# Main.net
KiCad netlist of a schematic drawn in Altium Designer
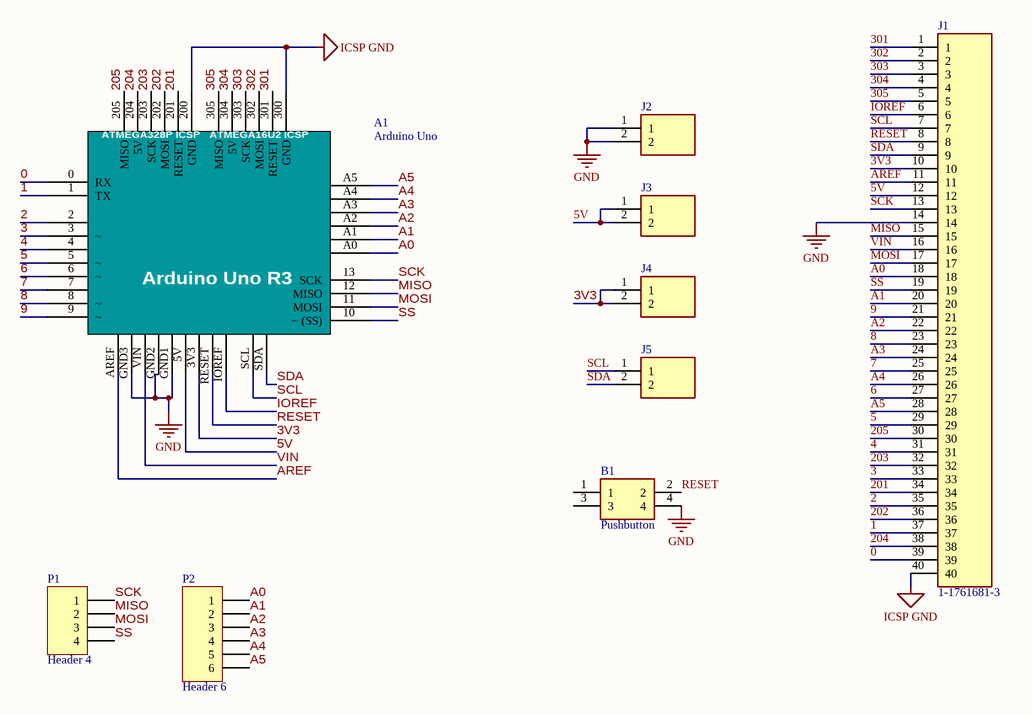
[diagram p0: Main.SchDoc]

(export (version "E")
  (design (tool "Eeschema 10.0.6"))
  (components
    (comp (ref "A1")
      (value "Arduino Uno")
      (footprint "Arduino Uno")
      (libsource (lib "Detailed Arduino") (part "Arduino Uno"))
    )
    (comp (ref "B1")
      (value "Pushbutton")
      (footprint "SamacSys:FSM4JH")
      (description "Switch")
      (fields
        (field (name "MANUFACTURER_PART_NUMBER") "FSM2JAH")
        (field (name "MOUSER PART NUMBER") "506-FSM2JAH")
      )
      (libsource (lib "SamacSys") (part "Pushbutton"))
    )
    (comp (ref "J1")
      (value "1-1761681-3")
      (footprint "TE_1-1761681-3")
      (description "IDC LOW PRO HDR 50P VERT HT BLACK")
      (libsource (lib "Molex 40pin Connector") (part "1-1761681-3"))
    )
    (comp (ref "J2")
      (value "TB002-500-02BE")
      (footprint "SamacSys:TB00250002BE")
      (description "Connector")
      (fields (field (name "MOUSER PART NUMBER") "490-TB002-500-02BE"))
      (libsource (lib "SamacSys") (part "TB002-500-02BE"))
    )
    (comp (ref "J3")
      (value "TB002-500-02BE")
      (footprint "SamacSys:TB00250002BE")
      (description "Connector")
      (fields (field (name "MOUSER PART NUMBER") "490-TB002-500-02BE"))
      (libsource (lib "SamacSys") (part "TB002-500-02BE"))
    )
    (comp (ref "J4")
      (value "TB002-500-02BE")
      (footprint "SamacSys:TB00250002BE")
      (description "Connector")
      (fields (field (name "MOUSER PART NUMBER") "490-TB002-500-02BE"))
      (libsource (lib "SamacSys") (part "TB002-500-02BE"))
    )
    (comp (ref "J5")
      (value "TB002-500-02BE")
      (footprint "SamacSys:TB00250002BE")
      (description "Connector")
      (fields (field (name "MOUSER PART NUMBER") "490-TB002-500-02BE"))
      (libsource (lib "SamacSys") (part "TB002-500-02BE"))
    )
    (comp (ref "P1")
      (value "Header 4")
      (footprint "HDR1X4")
      (description "Header, 4-Pin")
      (fields (field (name "PUBLISHER") "Altium Limited"))
      (libsource (lib "Miscellaneous Connectors") (part "Header 4"))
    )
    (comp (ref "P2")
      (value "Header 6")
      (footprint "HDR1X6")
      (description "Header, 6-Pin")
      (fields (field (name "PUBLISHER") "Altium Limited"))
      (libsource (lib "Miscellaneous Connectors") (part "Header 6"))
    )
  )
  (nets
    (net (code "1") (name "/0") (class "Default")
      (node (ref "A1") (pin "0") (pinfunction "RX_0") (pintype "power_in"))
      (node (ref "J1") (pin "39") (pinfunction "39_39") (pintype "passive"))
    )
    (net (code "2") (name "/1") (class "Default")
      (node (ref "A1") (pin "1") (pinfunction "TX_1") (pintype "power_in"))
      (node (ref "J1") (pin "37") (pinfunction "37_37") (pintype "passive"))
    )
    (net (code "3") (name "/2") (class "Default")
      (node (ref "A1") (pin "2") (pintype "power_in"))
      (node (ref "J1") (pin "35") (pinfunction "35_35") (pintype "passive"))
    )
    (net (code "4") (name "/3") (class "Default")
      (node (ref "A1") (pin "3") (pinfunction "~_3") (pintype "power_in"))
      (node (ref "J1") (pin "33") (pinfunction "33_33") (pintype "passive"))
    )
    (net (code "5") (name "/3V3") (class "Default")
      (node (ref "A1") (pin "3V3") (pintype "power_in"))
      (node (ref "J1") (pin "10") (pinfunction "10_10") (pintype "passive"))
      (node (ref "J4") (pin "1") (pinfunction "1_1") (pintype "passive"))
      (node (ref "J4") (pin "2") (pinfunction "2_2") (pintype "passive"))
    )
    (net (code "6") (name "/4") (class "Default")
      (node (ref "A1") (pin "4") (pintype "power_in"))
      (node (ref "J1") (pin "31") (pinfunction "31_31") (pintype "passive"))
    )
    (net (code "7") (name "/5") (class "Default")
      (node (ref "A1") (pin "5") (pinfunction "~_5") (pintype "power_in"))
      (node (ref "J1") (pin "29") (pinfunction "29_29") (pintype "passive"))
    )
    (net (code "8") (name "/5V") (class "Default")
      (node (ref "A1") (pin "5V") (pintype "power_in"))
      (node (ref "J1") (pin "12") (pinfunction "12_12") (pintype "passive"))
      (node (ref "J3") (pin "1") (pinfunction "1_1") (pintype "passive"))
      (node (ref "J3") (pin "2") (pinfunction "2_2") (pintype "passive"))
    )
    (net (code "9") (name "/6") (class "Default")
      (node (ref "A1") (pin "6") (pinfunction "~_6") (pintype "power_in"))
      (node (ref "J1") (pin "27") (pinfunction "27_27") (pintype "passive"))
    )
    (net (code "10") (name "/7") (class "Default")
      (node (ref "A1") (pin "7") (pintype "power_in"))
      (node (ref "J1") (pin "25") (pinfunction "25_25") (pintype "passive"))
    )
    (net (code "11") (name "/8") (class "Default")
      (node (ref "A1") (pin "8") (pinfunction "~_8") (pintype "power_in"))
      (node (ref "J1") (pin "23") (pinfunction "23_23") (pintype "passive"))
    )
    (net (code "12") (name "/9") (class "Default")
      (node (ref "A1") (pin "9") (pinfunction "~_9") (pintype "power_in"))
      (node (ref "J1") (pin "21") (pinfunction "21_21") (pintype "passive"))
    )
    (net (code "13") (name "/201") (class "Default")
      (node (ref "A1") (pin "201") (pinfunction "RESET_201") (pintype "power_in"))
      (node (ref "J1") (pin "34") (pinfunction "34_34") (pintype "passive"))
    )
    (net (code "14") (name "/202") (class "Default")
      (node (ref "A1") (pin "202") (pinfunction "MOSI_202") (pintype "power_in"))
      (node (ref "J1") (pin "36") (pinfunction "36_36") (pintype "passive"))
    )
    (net (code "15") (name "/203") (class "Default")
      (node (ref "A1") (pin "203") (pinfunction "SCK_203") (pintype "power_in"))
      (node (ref "J1") (pin "32") (pinfunction "32_32") (pintype "passive"))
    )
    (net (code "16") (name "/204") (class "Default")
      (node (ref "A1") (pin "204") (pinfunction "5V_204") (pintype "power_in"))
      (node (ref "J1") (pin "38") (pinfunction "38_38") (pintype "passive"))
    )
    (net (code "17") (name "/205") (class "Default")
      (node (ref "A1") (pin "205") (pinfunction "MISO_205") (pintype "power_in"))
      (node (ref "J1") (pin "30") (pinfunction "30_30") (pintype "passive"))
    )
    (net (code "18") (name "/301") (class "Default")
      (node (ref "A1") (pin "301") (pinfunction "RESET_301") (pintype "power_in"))
      (node (ref "J1") (pin "1") (pinfunction "1_1") (pintype "passive"))
    )
    (net (code "19") (name "/302") (class "Default")
      (node (ref "A1") (pin "302") (pinfunction "MOSI_302") (pintype "power_in"))
      (node (ref "J1") (pin "2") (pinfunction "2_2") (pintype "passive"))
    )
    (net (code "20") (name "/303") (class "Default")
      (node (ref "A1") (pin "303") (pinfunction "SCK_303") (pintype "power_in"))
      (node (ref "J1") (pin "3") (pinfunction "3_3") (pintype "passive"))
    )
    (net (code "21") (name "/304") (class "Default")
      (node (ref "A1") (pin "304") (pinfunction "5V_304") (pintype "power_in"))
      (node (ref "J1") (pin "4") (pinfunction "4_4") (pintype "passive"))
    )
    (net (code "22") (name "/305") (class "Default")
      (node (ref "A1") (pin "305") (pinfunction "MISO_305") (pintype "power_in"))
      (node (ref "J1") (pin "5") (pinfunction "5_5") (pintype "passive"))
    )
    (net (code "23") (name "/A0") (class "Default")
      (node (ref "A1") (pin "A0") (pintype "power_in"))
      (node (ref "J1") (pin "18") (pinfunction "18_18") (pintype "passive"))
      (node (ref "P2") (pin "1") (pinfunction "1_1") (pintype "passive"))
    )
    (net (code "24") (name "/A1") (class "Default")
      (node (ref "A1") (pin "A1") (pintype "power_in"))
      (node (ref "J1") (pin "20") (pinfunction "20_20") (pintype "passive"))
      (node (ref "P2") (pin "2") (pinfunction "2_2") (pintype "passive"))
    )
    (net (code "25") (name "/A2") (class "Default")
      (node (ref "A1") (pin "A2") (pintype "power_in"))
      (node (ref "J1") (pin "22") (pinfunction "22_22") (pintype "passive"))
      (node (ref "P2") (pin "3") (pinfunction "3_3") (pintype "passive"))
    )
    (net (code "26") (name "/A3") (class "Default")
      (node (ref "A1") (pin "A3") (pintype "power_in"))
      (node (ref "J1") (pin "24") (pinfunction "24_24") (pintype "passive"))
      (node (ref "P2") (pin "4") (pinfunction "4_4") (pintype "passive"))
    )
    (net (code "27") (name "/A4") (class "Default")
      (node (ref "A1") (pin "A4") (pintype "power_in"))
      (node (ref "J1") (pin "26") (pinfunction "26_26") (pintype "passive"))
      (node (ref "P2") (pin "5") (pinfunction "5_5") (pintype "passive"))
    )
    (net (code "28") (name "/A5") (class "Default")
      (node (ref "A1") (pin "A5") (pintype "power_in"))
      (node (ref "J1") (pin "28") (pinfunction "28_28") (pintype "passive"))
      (node (ref "P2") (pin "6") (pinfunction "6_6") (pintype "passive"))
    )
    (net (code "29") (name "/AREF") (class "Default")
      (node (ref "A1") (pin "AREF") (pintype "power_in"))
      (node (ref "J1") (pin "11") (pinfunction "11_11") (pintype "passive"))
    )
    (net (code "30") (name "/IOREF") (class "Default")
      (node (ref "A1") (pin "IOREF") (pintype "power_in"))
      (node (ref "J1") (pin "6") (pinfunction "6_6") (pintype "passive"))
    )
    (net (code "31") (name "/MISO") (class "Default")
      (node (ref "A1") (pin "12") (pinfunction "MISO_12") (pintype "power_in"))
      (node (ref "J1") (pin "15") (pinfunction "15_15") (pintype "passive"))
      (node (ref "P1") (pin "2") (pinfunction "2_2") (pintype "passive"))
    )
    (net (code "32") (name "/MOSI") (class "Default")
      (node (ref "A1") (pin "11") (pinfunction "MOSI_11") (pintype "power_in"))
      (node (ref "J1") (pin "17") (pinfunction "17_17") (pintype "passive"))
      (node (ref "P1") (pin "3") (pinfunction "3_3") (pintype "passive"))
    )
    (net (code "33") (name "/RESET") (class "Default")
      (node (ref "A1") (pin "RESET") (pintype "power_in"))
      (node (ref "B1") (pin "2") (pinfunction "2_2") (pintype "passive"))
      (node (ref "J1") (pin "8") (pinfunction "8_8") (pintype "passive"))
    )
    (net (code "34") (name "/SCK") (class "Default")
      (node (ref "A1") (pin "13") (pinfunction "SCK_13") (pintype "power_in"))
      (node (ref "J1") (pin "13") (pinfunction "13_13") (pintype "passive"))
      (node (ref "P1") (pin "1") (pinfunction "1_1") (pintype "passive"))
    )
    (net (code "35") (name "/SCL") (class "Default")
      (node (ref "A1") (pin "SCL") (pintype "power_in"))
      (node (ref "J1") (pin "7") (pinfunction "7_7") (pintype "passive"))
      (node (ref "J5") (pin "1") (pinfunction "1_1") (pintype "passive"))
    )
    (net (code "36") (name "/SDA") (class "Default")
      (node (ref "A1") (pin "SDA") (pintype "power_in"))
      (node (ref "J1") (pin "9") (pinfunction "9_9") (pintype "passive"))
      (node (ref "J5") (pin "2") (pinfunction "2_2") (pintype "passive"))
    )
    (net (code "37") (name "/SS") (class "Default")
      (node (ref "A1") (pin "10") (pinfunction "~_(SS)_10") (pintype "power_in"))
      (node (ref "J1") (pin "19") (pinfunction "19_19") (pintype "passive"))
      (node (ref "P1") (pin "4") (pinfunction "4_4") (pintype "passive"))
    )
    (net (code "38") (name "/VIN") (class "Default")
      (node (ref "A1") (pin "VIN") (pintype "power_in"))
      (node (ref "J1") (pin "16") (pinfunction "16_16") (pintype "passive"))
    )
    (net (code "39") (name "GND") (class "Default")
      (node (ref "A1") (pin "GND1") (pintype "power_in"))
      (node (ref "A1") (pin "GND2") (pintype "power_in"))
      (node (ref "A1") (pin "GND3") (pintype "power_in"))
      (node (ref "B1") (pin "4") (pinfunction "4_4") (pintype "passive"))
      (node (ref "J1") (pin "14") (pinfunction "14_14") (pintype "passive"))
      (node (ref "J2") (pin "1") (pinfunction "1_1") (pintype "passive"))
      (node (ref "J2") (pin "2") (pinfunction "2_2") (pintype "passive"))
    )
    (net (code "40") (name "ICSP GND") (class "Default")
      (node (ref "A1") (pin "200") (pinfunction "GND_200") (pintype "power_in"))
      (node (ref "A1") (pin "300") (pinfunction "GND_300") (pintype "power_in"))
      (node (ref "J1") (pin "40") (pinfunction "40_40") (pintype "passive"))
    )
    (net (code "41") (name "unconnected-(B1-Pad1)") (class "Default")
      (node (ref "B1") (pin "1") (pinfunction "1_1") (pintype "passive"))
    )
    (net (code "42") (name "unconnected-(B1-Pad3)") (class "Default")
      (node (ref "B1") (pin "3") (pinfunction "3_3") (pintype "passive"))
    )
  )
)
